# Motor_Drivers.net
KiCad netlist of a schematic drawn in Altium Designer
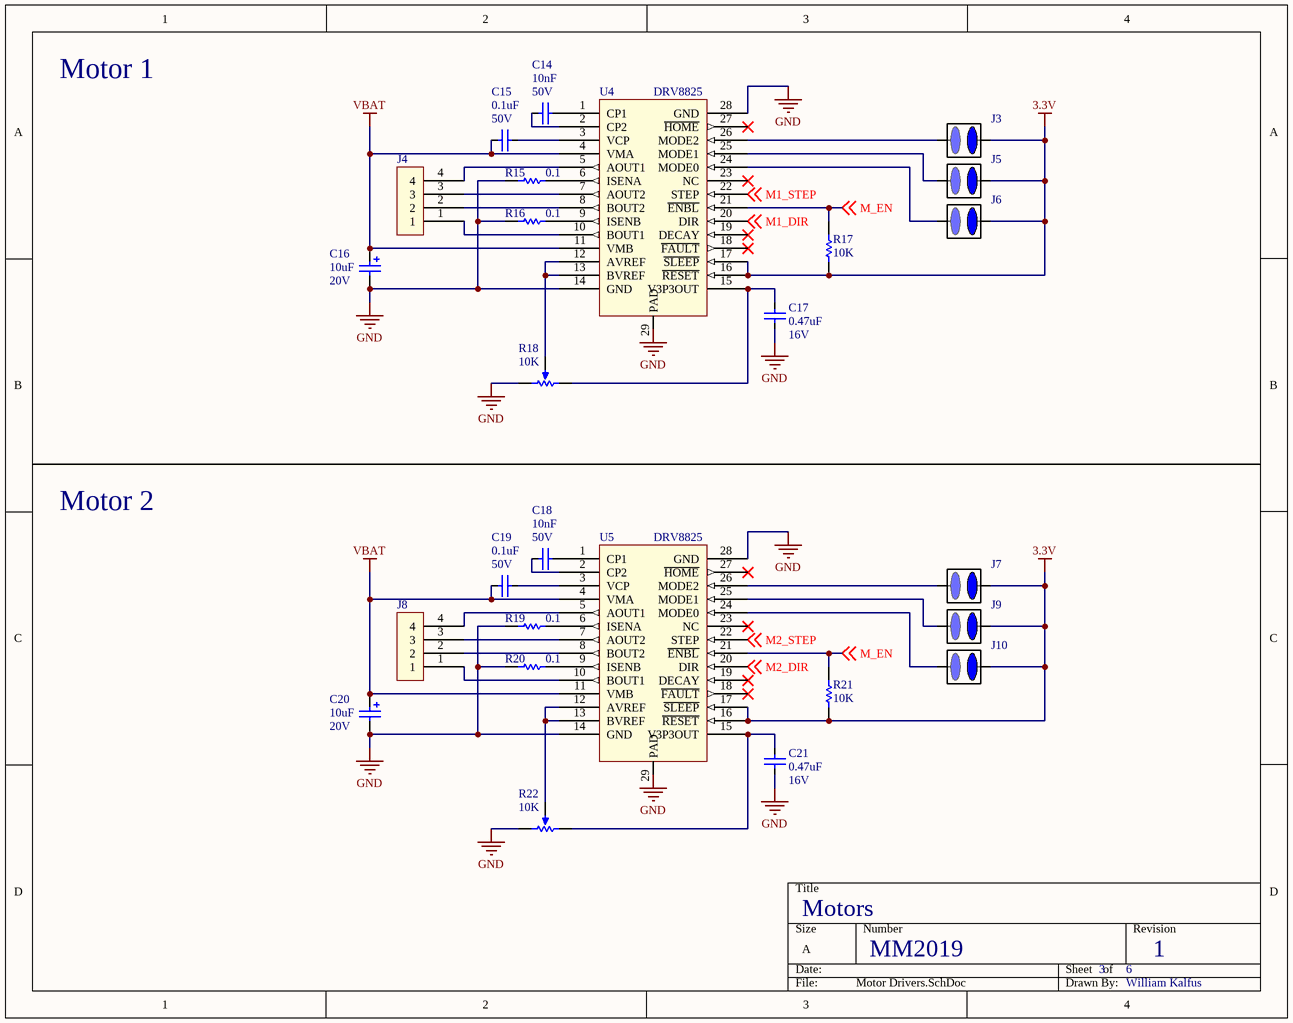
[diagram p0: Motor Drivers.SchDoc]

(export (version "E")
  (design (tool "Eeschema 10.0.6"))
  (components
    (comp (ref "C14")
      (value "10nF")
      (footprint "J1-0603")
      (description "CAP CER 10000PF 50V X7R 0603")
      (fields (field (name "VOLTAGE RATING") "50V") (field (name "Comment") "CAP"))
      (libsource (lib "Components") (part "CAP"))
    )
    (comp (ref "C15")
      (value "0.1uF")
      (footprint "J1-0603")
      (description "CAP CER 0.1UF 50V X7R 0603")
      (fields (field (name "VOLTAGE RATING") "50V") (field (name "Comment") "CAP"))
      (libsource (lib "Components") (part "CAP"))
    )
    (comp (ref "C16")
      (value "10uF")
      (footprint "1206+")
      (description "CAP TANT 10UF 10% 20V 1206")
      (fields
        (field (name "VOLTAGE RATING") "20V")
        (field (name "Comment") "CAP POL")
        (field (name "PUBLISHER") "Altium Limited")
      )
      (libsource (lib "MicromouseLib") (part "CAP POL"))
    )
    (comp (ref "C17")
      (value "0.47uF")
      (footprint "J1-0603")
      (description "CAP CER 0.47UF 16V X7R 0603")
      (fields (field (name "VOLTAGE RATING") "16V") (field (name "Comment") "CAP"))
      (libsource (lib "Components") (part "CAP"))
    )
    (comp (ref "C18")
      (value "10nF")
      (footprint "J1-0603")
      (description "CAP CER 10000PF 50V X7R 0603")
      (fields (field (name "VOLTAGE RATING") "50V") (field (name "Comment") "CAP"))
      (libsource (lib "Components") (part "CAP"))
    )
    (comp (ref "C19")
      (value "0.1uF")
      (footprint "J1-0603")
      (description "CAP CER 0.1UF 50V X7R 0603")
      (fields (field (name "VOLTAGE RATING") "50V") (field (name "Comment") "CAP"))
      (libsource (lib "Components") (part "CAP"))
    )
    (comp (ref "C20")
      (value "10uF")
      (footprint "1206+")
      (description "CAP TANT 10UF 10% 20V 1206")
      (fields
        (field (name "VOLTAGE RATING") "20V")
        (field (name "Comment") "CAP POL")
        (field (name "PUBLISHER") "Altium Limited")
      )
      (libsource (lib "MicromouseLib") (part "CAP POL"))
    )
    (comp (ref "C21")
      (value "0.47uF")
      (footprint "J1-0603")
      (description "CAP CER 0.47UF 16V X7R 0603")
      (fields (field (name "VOLTAGE RATING") "16V") (field (name "Comment") "CAP"))
      (libsource (lib "Components") (part "CAP"))
    )
    (comp (ref "J3") (value "JUMPER") (footprint "JUMPER") (libsource (lib "MicromouseLib") (part "JUMPER")))
    (comp (ref "J4")
      (value "CONN_4x1")
      (footprint "CONN_4x1")
      (description "CONN HEADER 4POS .100 R/A 30AU")
      (fields
        (field (name "MANUFACTURER") "Amphenol FCI")
        (field (name "MANUFACTURER PART NUMBER") "68016-104HLF")
      )
      (libsource (lib "MicromouseLib") (part "CONN_4x1"))
    )
    (comp (ref "J5") (value "JUMPER") (footprint "JUMPER") (libsource (lib "MicromouseLib") (part "JUMPER")))
    (comp (ref "J6") (value "JUMPER") (footprint "JUMPER") (libsource (lib "MicromouseLib") (part "JUMPER")))
    (comp (ref "J7") (value "JUMPER") (footprint "JUMPER") (libsource (lib "MicromouseLib") (part "JUMPER")))
    (comp (ref "J8")
      (value "CONN_4x1")
      (footprint "CONN_4x1")
      (description "CONN HEADER 4POS .100 R/A 30AU")
      (fields
        (field (name "MANUFACTURER") "Amphenol FCI")
        (field (name "MANUFACTURER PART NUMBER") "68016-104HLF")
      )
      (libsource (lib "MicromouseLib") (part "CONN_4x1"))
    )
    (comp (ref "J9") (value "JUMPER") (footprint "JUMPER") (libsource (lib "MicromouseLib") (part "JUMPER")))
    (comp (ref "J10") (value "JUMPER") (footprint "JUMPER") (libsource (lib "MicromouseLib") (part "JUMPER")))
    (comp (ref "R15")
      (value "0.1")
      (footprint "J1-0603")
      (description "RES 0.1 OHM 1% 1/3W 0603")
      (libsource (lib "Miscellaneous Devices") (part "Res1"))
    )
    (comp (ref "R16")
      (value "0.1")
      (footprint "J1-0603")
      (description "RES 0.1 OHM 1% 1/3W 0603")
      (libsource (lib "Miscellaneous Devices") (part "Res1"))
    )
    (comp (ref "R17")
      (value "10K")
      (footprint "J1-0603")
      (description "RES SMD 10K OHM 5% 1/10W 0603")
      (libsource (lib "Miscellaneous Devices") (part "Res1"))
    )
    (comp (ref "R18")
      (value "10K")
      (footprint "ST32-EB")
      (description "10K Trimmer Potentiometer")
      (fields (field (name "Comment") "POT ST32ETB103") (field (name "PUBLISHER") "Altium Limited"))
      (libsource (lib "MicromouseLib") (part "POT ST32ETB103"))
    )
    (comp (ref "R19")
      (value "0.1")
      (footprint "J1-0603")
      (description "RES 0.1 OHM 1% 1/3W 0603")
      (libsource (lib "Miscellaneous Devices") (part "Res1"))
    )
    (comp (ref "R20")
      (value "0.1")
      (footprint "J1-0603")
      (description "RES 0.1 OHM 1% 1/3W 0603")
      (libsource (lib "Miscellaneous Devices") (part "Res1"))
    )
    (comp (ref "R21")
      (value "10K")
      (footprint "J1-0603")
      (description "RES SMD 10K OHM 5% 1/10W 0603")
      (libsource (lib "Miscellaneous Devices") (part "Res1"))
    )
    (comp (ref "R22")
      (value "10K")
      (footprint "ST32-EB")
      (description "10K Trimmer Potentiometer")
      (fields (field (name "Comment") "POT ST32ETB103") (field (name "PUBLISHER") "Altium Limited"))
      (libsource (lib "MicromouseLib") (part "POT ST32ETB103"))
    )
    (comp (ref "U4")
      (value "DRV8825")
      (footprint "PP28")
      (description "IC MOTOR DRIVER PAR 28HTSSOP")
      (fields
        (field (name "MANUFACTURER") "Texas Instruments")
        (field (name "MANUFACTURER PART NUMBER") "DRV8825PWPR")
      )
      (libsource (lib "MicromouseLib") (part "DRV8825"))
    )
    (comp (ref "U5")
      (value "DRV8825")
      (footprint "PP28")
      (description "IC MOTOR DRIVER PAR 28HTSSOP")
      (fields
        (field (name "MANUFACTURER") "Texas Instruments")
        (field (name "MANUFACTURER PART NUMBER") "DRV8825PWPR")
      )
      (libsource (lib "MicromouseLib") (part "DRV8825"))
    )
  )
  (nets
    (net (code "1") (name "3.3V") (class "Default")
      (node (ref "J10") (pin "2") (pintype "passive"))
      (node (ref "J3") (pin "2") (pintype "passive"))
      (node (ref "J5") (pin "2") (pintype "passive"))
      (node (ref "J6") (pin "2") (pintype "passive"))
      (node (ref "J7") (pin "2") (pintype "passive"))
      (node (ref "J9") (pin "2") (pintype "passive"))
      (node (ref "R17") (pin "2") (pinfunction "2_2") (pintype "passive"))
      (node (ref "R21") (pin "2") (pinfunction "2_2") (pintype "passive"))
      (node (ref "U4") (pin "16") (pinfunction "~{RESET}_16") (pintype "input"))
      (node (ref "U4") (pin "17") (pinfunction "~{SLEEP}_17") (pintype "input"))
      (node (ref "U5") (pin "16") (pinfunction "~{RESET}_16") (pintype "input"))
      (node (ref "U5") (pin "17") (pinfunction "~{SLEEP}_17") (pintype "input"))
    )
    (net (code "2") (name "GND") (class "Default")
      (node (ref "C16") (pin "2") (pinfunction "2_2") (pintype "passive"))
      (node (ref "C17") (pin "2") (pinfunction "2_2") (pintype "passive"))
      (node (ref "C20") (pin "2") (pinfunction "2_2") (pintype "passive"))
      (node (ref "C21") (pin "2") (pinfunction "2_2") (pintype "passive"))
      (node (ref "R15") (pin "2") (pinfunction "2_2") (pintype "passive"))
      (node (ref "R16") (pin "2") (pinfunction "2_2") (pintype "passive"))
      (node (ref "R18") (pin "3") (pinfunction "BOT_3") (pintype "passive"))
      (node (ref "R19") (pin "2") (pinfunction "2_2") (pintype "passive"))
      (node (ref "R20") (pin "2") (pinfunction "2_2") (pintype "passive"))
      (node (ref "R22") (pin "3") (pinfunction "BOT_3") (pintype "passive"))
      (node (ref "U4") (pin "14") (pinfunction "GND_14") (pintype "power_in"))
      (node (ref "U4") (pin "28") (pinfunction "GND_28") (pintype "passive"))
      (node (ref "U4") (pin "29") (pinfunction "PAD_29") (pintype "power_in"))
      (node (ref "U5") (pin "14") (pinfunction "GND_14") (pintype "power_in"))
      (node (ref "U5") (pin "28") (pinfunction "GND_28") (pintype "passive"))
      (node (ref "U5") (pin "29") (pinfunction "PAD_29") (pintype "power_in"))
    )
    (net (code "3") (name "M1_DIR") (class "Default")
      (node (ref "U4") (pin "20") (pinfunction "DIR_20") (pintype "input"))
    )
    (net (code "4") (name "M1_STEP") (class "Default")
      (node (ref "U4") (pin "22") (pinfunction "STEP_22") (pintype "input"))
    )
    (net (code "5") (name "M2_DIR") (class "Default")
      (node (ref "U5") (pin "20") (pinfunction "DIR_20") (pintype "input"))
    )
    (net (code "6") (name "M2_STEP") (class "Default")
      (node (ref "U5") (pin "22") (pinfunction "STEP_22") (pintype "input"))
    )
    (net (code "7") (name "M_EN") (class "Default")
      (node (ref "R17") (pin "1") (pinfunction "1_1") (pintype "passive"))
      (node (ref "R21") (pin "1") (pinfunction "1_1") (pintype "passive"))
      (node (ref "U4") (pin "21") (pinfunction "~{ENBL}_21") (pintype "input"))
      (node (ref "U5") (pin "21") (pinfunction "~{ENBL}_21") (pintype "input"))
    )
    (net (code "8") (name "Net-(R18-TAP)") (class "Default")
      (node (ref "R18") (pin "2") (pinfunction "TAP_2") (pintype "passive"))
      (node (ref "U4") (pin "12") (pinfunction "AVREF_12") (pintype "power_in"))
      (node (ref "U4") (pin "13") (pinfunction "BVREF_13") (pintype "power_in"))
    )
    (net (code "9") (name "Net-(R18-TOP)") (class "Default")
      (node (ref "C17") (pin "1") (pinfunction "1_1") (pintype "passive"))
      (node (ref "R18") (pin "1") (pinfunction "TOP_1") (pintype "passive"))
      (node (ref "U4") (pin "15") (pinfunction "V3P3OUT_15") (pintype "power_in"))
    )
    (net (code "10") (name "Net-(R22-TAP)") (class "Default")
      (node (ref "R22") (pin "2") (pinfunction "TAP_2") (pintype "passive"))
      (node (ref "U5") (pin "12") (pinfunction "AVREF_12") (pintype "power_in"))
      (node (ref "U5") (pin "13") (pinfunction "BVREF_13") (pintype "power_in"))
    )
    (net (code "11") (name "Net-(R22-TOP)") (class "Default")
      (node (ref "C21") (pin "1") (pinfunction "1_1") (pintype "passive"))
      (node (ref "R22") (pin "1") (pinfunction "TOP_1") (pintype "passive"))
      (node (ref "U5") (pin "15") (pinfunction "V3P3OUT_15") (pintype "power_in"))
    )
    (net (code "12") (name "Net-(U4-AOUT1)") (class "Default")
      (node (ref "J4") (pin "4") (pinfunction "4_4") (pintype "passive"))
      (node (ref "U4") (pin "5") (pinfunction "AOUT1_5") (pintype "output"))
    )
    (net (code "13") (name "Net-(U4-AOUT2)") (class "Default")
      (node (ref "J4") (pin "3") (pinfunction "3_3") (pintype "passive"))
      (node (ref "U4") (pin "7") (pinfunction "AOUT2_7") (pintype "output"))
    )
    (net (code "14") (name "Net-(U4-BOUT1)") (class "Default")
      (node (ref "J4") (pin "1") (pinfunction "1_1") (pintype "passive"))
      (node (ref "U4") (pin "10") (pinfunction "BOUT1_10") (pintype "output"))
    )
    (net (code "15") (name "Net-(U4-BOUT2)") (class "Default")
      (node (ref "J4") (pin "2") (pinfunction "2_2") (pintype "passive"))
      (node (ref "U4") (pin "8") (pinfunction "BOUT2_8") (pintype "output"))
    )
    (net (code "16") (name "Net-(U4-CP1)") (class "Default")
      (node (ref "C14") (pin "1") (pinfunction "1_1") (pintype "passive"))
      (node (ref "U4") (pin "1") (pinfunction "CP1_1") (pintype "passive"))
    )
    (net (code "17") (name "Net-(U4-CP2)") (class "Default")
      (node (ref "C14") (pin "2") (pinfunction "2_2") (pintype "passive"))
      (node (ref "U4") (pin "2") (pinfunction "CP2_2") (pintype "passive"))
    )
    (net (code "18") (name "Net-(U4-ISENA)") (class "Default")
      (node (ref "R15") (pin "1") (pinfunction "1_1") (pintype "passive"))
      (node (ref "U4") (pin "6") (pinfunction "ISENA_6") (pintype "output"))
    )
    (net (code "19") (name "Net-(U4-ISENB)") (class "Default")
      (node (ref "R16") (pin "1") (pinfunction "1_1") (pintype "passive"))
      (node (ref "U4") (pin "9") (pinfunction "ISENB_9") (pintype "output"))
    )
    (net (code "20") (name "Net-(U4-MODE0)") (class "Default")
      (node (ref "J6") (pin "1") (pintype "passive"))
      (node (ref "U4") (pin "24") (pinfunction "MODE0_24") (pintype "input"))
    )
    (net (code "21") (name "Net-(U4-MODE1)") (class "Default")
      (node (ref "J5") (pin "1") (pintype "passive"))
      (node (ref "U4") (pin "25") (pinfunction "MODE1_25") (pintype "input"))
    )
    (net (code "22") (name "Net-(U4-MODE2)") (class "Default")
      (node (ref "J3") (pin "1") (pintype "passive"))
      (node (ref "U4") (pin "26") (pinfunction "MODE2_26") (pintype "input"))
    )
    (net (code "23") (name "Net-(U4-VCP)") (class "Default")
      (node (ref "C15") (pin "1") (pinfunction "1_1") (pintype "passive"))
      (node (ref "U4") (pin "3") (pinfunction "VCP_3") (pintype "power_in"))
    )
    (net (code "24") (name "Net-(U5-AOUT1)") (class "Default")
      (node (ref "J8") (pin "4") (pinfunction "4_4") (pintype "passive"))
      (node (ref "U5") (pin "5") (pinfunction "AOUT1_5") (pintype "output"))
    )
    (net (code "25") (name "Net-(U5-AOUT2)") (class "Default")
      (node (ref "J8") (pin "3") (pinfunction "3_3") (pintype "passive"))
      (node (ref "U5") (pin "7") (pinfunction "AOUT2_7") (pintype "output"))
    )
    (net (code "26") (name "Net-(U5-BOUT1)") (class "Default")
      (node (ref "J8") (pin "1") (pinfunction "1_1") (pintype "passive"))
      (node (ref "U5") (pin "10") (pinfunction "BOUT1_10") (pintype "output"))
    )
    (net (code "27") (name "Net-(U5-BOUT2)") (class "Default")
      (node (ref "J8") (pin "2") (pinfunction "2_2") (pintype "passive"))
      (node (ref "U5") (pin "8") (pinfunction "BOUT2_8") (pintype "output"))
    )
    (net (code "28") (name "Net-(U5-CP1)") (class "Default")
      (node (ref "C18") (pin "1") (pinfunction "1_1") (pintype "passive"))
      (node (ref "U5") (pin "1") (pinfunction "CP1_1") (pintype "passive"))
    )
    (net (code "29") (name "Net-(U5-CP2)") (class "Default")
      (node (ref "C18") (pin "2") (pinfunction "2_2") (pintype "passive"))
      (node (ref "U5") (pin "2") (pinfunction "CP2_2") (pintype "passive"))
    )
    (net (code "30") (name "Net-(U5-ISENA)") (class "Default")
      (node (ref "R19") (pin "1") (pinfunction "1_1") (pintype "passive"))
      (node (ref "U5") (pin "6") (pinfunction "ISENA_6") (pintype "output"))
    )
    (net (code "31") (name "Net-(U5-ISENB)") (class "Default")
      (node (ref "R20") (pin "1") (pinfunction "1_1") (pintype "passive"))
      (node (ref "U5") (pin "9") (pinfunction "ISENB_9") (pintype "output"))
    )
    (net (code "32") (name "Net-(U5-MODE0)") (class "Default")
      (node (ref "J10") (pin "1") (pintype "passive"))
      (node (ref "U5") (pin "24") (pinfunction "MODE0_24") (pintype "input"))
    )
    (net (code "33") (name "Net-(U5-MODE1)") (class "Default")
      (node (ref "J9") (pin "1") (pintype "passive"))
      (node (ref "U5") (pin "25") (pinfunction "MODE1_25") (pintype "input"))
    )
    (net (code "34") (name "Net-(U5-MODE2)") (class "Default")
      (node (ref "J7") (pin "1") (pintype "passive"))
      (node (ref "U5") (pin "26") (pinfunction "MODE2_26") (pintype "input"))
    )
    (net (code "35") (name "Net-(U5-VCP)") (class "Default")
      (node (ref "C19") (pin "1") (pinfunction "1_1") (pintype "passive"))
      (node (ref "U5") (pin "3") (pinfunction "VCP_3") (pintype "power_in"))
    )
    (net (code "36") (name "VBAT") (class "Default")
      (node (ref "C15") (pin "2") (pinfunction "2_2") (pintype "passive"))
      (node (ref "C16") (pin "1") (pinfunction "1_1") (pintype "passive"))
      (node (ref "C19") (pin "2") (pinfunction "2_2") (pintype "passive"))
      (node (ref "C20") (pin "1") (pinfunction "1_1") (pintype "passive"))
      (node (ref "U4") (pin "11") (pinfunction "VMB_11") (pintype "power_in"))
      (node (ref "U4") (pin "4") (pinfunction "VMA_4") (pintype "power_in"))
      (node (ref "U5") (pin "11") (pinfunction "VMB_11") (pintype "power_in"))
      (node (ref "U5") (pin "4") (pinfunction "VMA_4") (pintype "power_in"))
    )
    (net (code "37") (name "unconnected-(U4-DECAY-Pad19)") (class "Default")
      (node (ref "U4") (pin "19") (pinfunction "DECAY_19") (pintype "input+no_connect"))
    )
    (net (code "38") (name "unconnected-(U4-NC-Pad23)") (class "Default")
      (node (ref "U4") (pin "23") (pinfunction "NC_23") (pintype "passive+no_connect"))
    )
    (net (code "39") (name "unconnected-(U4-~{FAULT}-Pad18)") (class "Default")
      (node (ref "U4") (pin "18") (pinfunction "~{FAULT}_18") (pintype "output+no_connect"))
    )
    (net (code "40") (name "unconnected-(U4-~{HOME}-Pad27)") (class "Default")
      (node (ref "U4") (pin "27") (pinfunction "~{HOME}_27") (pintype "output+no_connect"))
    )
    (net (code "41") (name "unconnected-(U5-DECAY-Pad19)") (class "Default")
      (node (ref "U5") (pin "19") (pinfunction "DECAY_19") (pintype "input+no_connect"))
    )
    (net (code "42") (name "unconnected-(U5-NC-Pad23)") (class "Default")
      (node (ref "U5") (pin "23") (pinfunction "NC_23") (pintype "passive+no_connect"))
    )
    (net (code "43") (name "unconnected-(U5-~{FAULT}-Pad18)") (class "Default")
      (node (ref "U5") (pin "18") (pinfunction "~{FAULT}_18") (pintype "output+no_connect"))
    )
    (net (code "44") (name "unconnected-(U5-~{HOME}-Pad27)") (class "Default")
      (node (ref "U5") (pin "27") (pinfunction "~{HOME}_27") (pintype "output+no_connect"))
    )
  )
)
